# Schematic_2023-04-14.net
KiCad netlist of a schematic drawn in Altium Designer
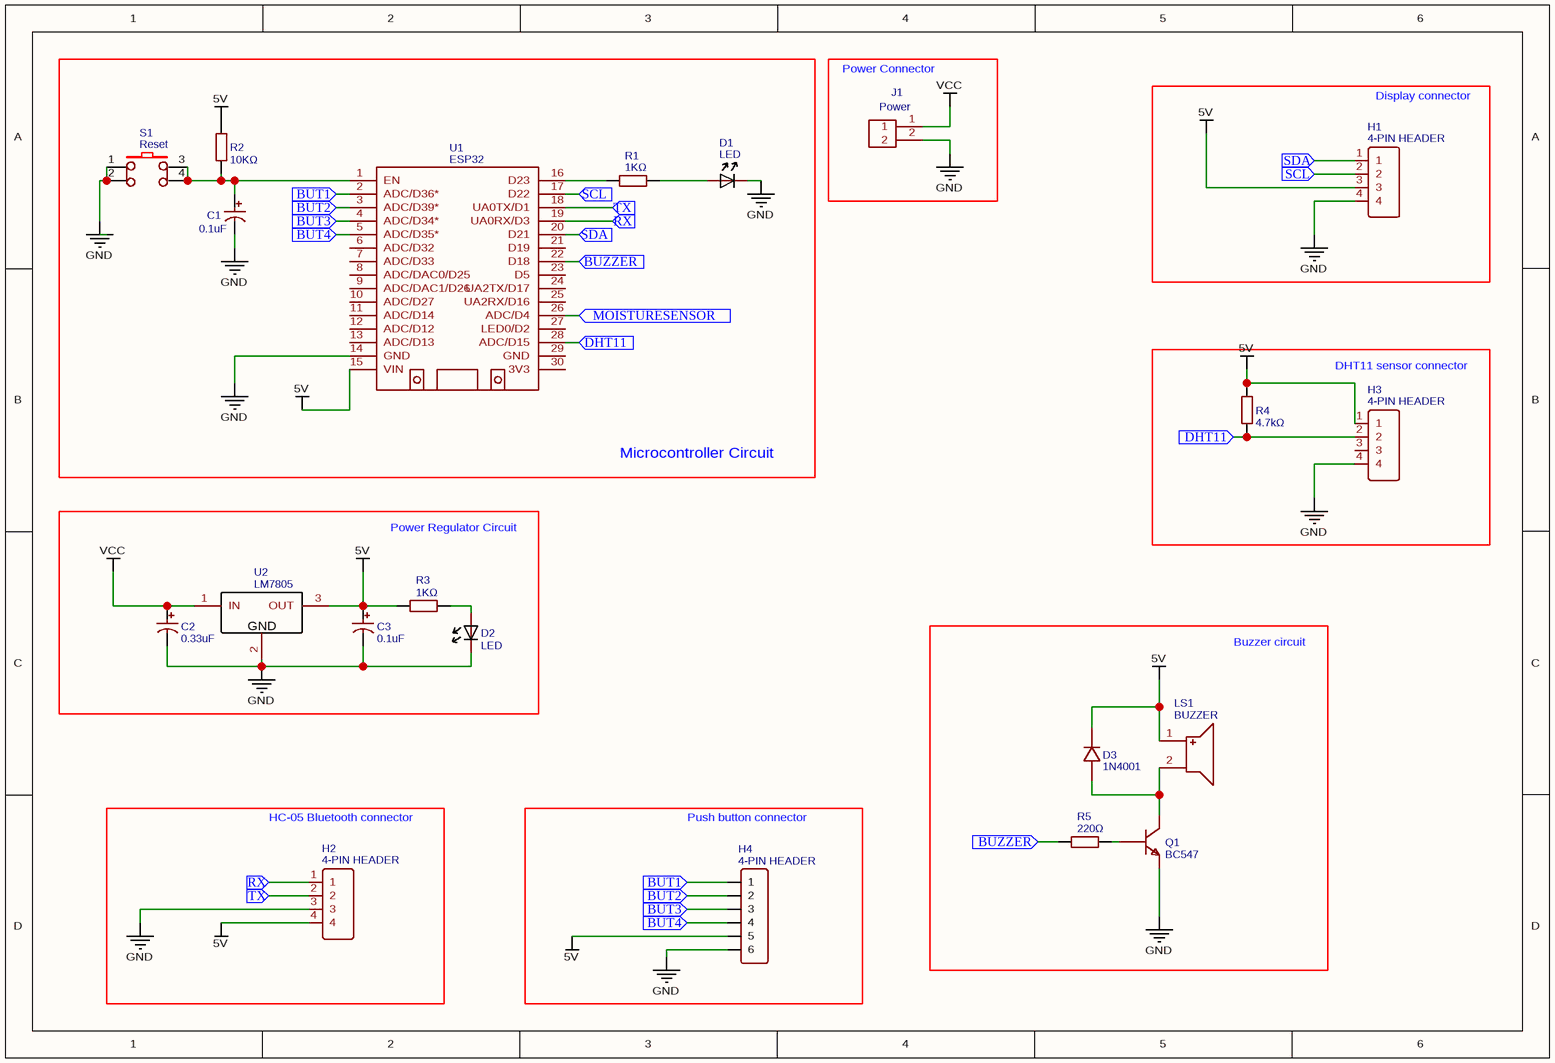
[diagram p0: Schematic_2023-04-14.schdoc]

(export (version "E")
  (design (tool "Eeschema 10.0.6"))
  (components
    (comp (ref "C1")
      (value "0.1uF")
      (fields (field (name "BOM_MANUFACTURER PART") "0.1UF 50V") (field (name "BOM_SUPPLIER PART") "C28061"))
      (libsource (lib "altium-import") (part "root_0_0.1uF_"))
    )
    (comp (ref "C2")
      (value "0.33uF")
      (fields
        (field (name "BOM_MANUFACTURER PART") "0.33uF 50V 5*11")
        (field (name "BOM_SUPPLIER PART") "C45097")
      )
      (libsource (lib "altium-import") (part "root_0_0.33uF_"))
    )
    (comp (ref "C3")
      (value "0.1uF")
      (fields (field (name "BOM_MANUFACTURER PART") "0.1UF 50V") (field (name "BOM_SUPPLIER PART") "C28061"))
      (libsource (lib "altium-import") (part "root_0_0.1uF_"))
    )
    (comp (ref "D1")
      (value "LED")
      (fields (field (name "BOM_MANUFACTURER PART") "5mm LED") (field (name "CONTRIBUTOR") "Axbri"))
      (libsource (lib "altium-import") (part "root_0_LED_"))
    )
    (comp (ref "D2")
      (value "LED")
      (fields (field (name "BOM_MANUFACTURER PART") "5mm LED") (field (name "CONTRIBUTOR") "Axbri"))
      (libsource (lib "altium-import") (part "root_3_LED_"))
    )
    (comp (ref "D3")
      (value "1N4001")
      (fields (field (name "BOM_SUPPLIER PART") "C99656") (field (name "CONTRIBUTOR") "LCSC"))
      (libsource (lib "altium-import") (part "root_3_1N4001_"))
    )
    (comp (ref "H1")
      (value "4-PIN HEADER")
      (fields (field (name "CONTRIBUTOR") "Kang Yi Te"))
      (libsource (lib "altium-import") (part "root_0_4-PIN HEADER_"))
    )
    (comp (ref "H2")
      (value "4-PIN HEADER")
      (fields (field (name "CONTRIBUTOR") "Kang Yi Te"))
      (libsource (lib "altium-import") (part "root_0_4-PIN HEADER_"))
    )
    (comp (ref "H3")
      (value "4-PIN HEADER")
      (fields (field (name "CONTRIBUTOR") "Kang Yi Te"))
      (libsource (lib "altium-import") (part "root_0_4-PIN HEADER_"))
    )
    (comp (ref "H4")
      (value "4-PIN HEADER")
      (fields (field (name "BOM_SUPPLIER PART") "C40877") (field (name "CONTRIBUTOR") "LCEDA_Lib"))
      (libsource (lib "") (part "root_0_4-PIN HEADER__1"))
    )
    (comp (ref "J1")
      (value "Power")
      (fields
        (field (name "BOM_MANUFACTURER PART") "XHB-2A Connector")
        (field (name "BOM_SUPPLIER PART") "C57981")
      )
      (libsource (lib "altium-import") (part "root_0_Power_"))
    )
    (comp (ref "LS1")
      (value "BUZZER")
      (fields
        (field (name "BOM_MANUFACTURER PART") "BUZZERHMB1206-03")
        (field (name "BOM_SUPPLIER PART") "C96101")
        (field (name "CONTRIBUTOR") "วริศรา เกรียงไกรวัฒน์ /ทิพพะ")
      )
      (libsource (lib "altium-import") (part "root_0_BUZZER_"))
    )
    (comp (ref "Q1")
      (value "BC547")
      (fields
        (field (name "BOM_SUPPLIER PART") "C900798")
        (field (name "BOM_MANUFACTURER PART") "BC547BTF")
        (field (name "CONTRIBUTOR") "LCSC")
      )
      (libsource (lib "altium-import") (part "root_0_BC547_"))
    )
    (comp (ref "R1")
      (value "1KΩ")
      (fields
        (field (name "POWER") "1/4W")
        (field (name "TOLERANCE") "±1%")
        (field (name "BOM_SUPPLIER PART") "E57439")
      )
      (libsource (lib "altium-import") (part "root_0_1KΩ_"))
    )
    (comp (ref "R2")
      (value "10KΩ")
      (fields
        (field (name "POWER") "1/4W")
        (field (name "TOLERANCE") "±1%")
        (field (name "BOM_SUPPLIER PART") "E57439")
      )
      (libsource (lib "altium-import") (part "root_3_10KΩ_"))
    )
    (comp (ref "R3")
      (value "1KΩ")
      (fields
        (field (name "POWER") "1/4W")
        (field (name "TOLERANCE") "±1%")
        (field (name "BOM_SUPPLIER PART") "E57439")
      )
      (libsource (lib "altium-import") (part "root_0_1KΩ_"))
    )
    (comp (ref "R4")
      (value "4.7kΩ")
      (fields
        (field (name "POWER") "1/4W")
        (field (name "TOLERANCE") "±1%")
        (field (name "BOM_SUPPLIER PART") "E57439")
      )
      (libsource (lib "altium-import") (part "root_3_4.7kΩ_"))
    )
    (comp (ref "R5")
      (value "220Ω")
      (fields
        (field (name "POWER") "1/4W")
        (field (name "TOLERANCE") "±1%")
        (field (name "BOM_SUPPLIER PART") "E57439")
      )
      (libsource (lib "altium-import") (part "root_0_220Ω_"))
    )
    (comp (ref "S1")
      (value "Reset")
      (fields
        (field (name "BOM_SUPPLIER PART") "C59980")
        (field (name "BOM_MANUFACTURER PART") "button6*6*8.5")
      )
      (libsource (lib "altium-import") (part "root_0_Reset_"))
    )
    (comp (ref "U1")
      (value "ESP32")
      (fields (field (name "CONTRIBUTOR") "ConceitoTeam"))
      (libsource (lib "altium-import") (part "root_0_ESP32_"))
    )
    (comp (ref "U2")
      (value "LM7805")
      (fields
        (field (name "BOM_MANUFACTURER PART") "L7805CV-DG")
        (field (name "BOM_SUPPLIER PART") "C3795")
        (field (name "CONTRIBUTOR") "LCEDA_Lib")
      )
      (libsource (lib "altium-import") (part "root_0_LM7805_"))
    )
  )
  (nets
    (net (code "1") (name "/BUT1") (class "Default")
      (node (ref "H4") (pin "1") (pinfunction "1_1") (pintype "passive"))
      (node (ref "U1") (pin "2") (pinfunction "ADC/D36*_2") (pintype "passive"))
    )
    (net (code "2") (name "/BUT2") (class "Default")
      (node (ref "H4") (pin "2") (pinfunction "2_2") (pintype "passive"))
      (node (ref "U1") (pin "3") (pinfunction "ADC/D39*_3") (pintype "passive"))
    )
    (net (code "3") (name "/BUT3") (class "Default")
      (node (ref "H4") (pin "3") (pinfunction "3_3") (pintype "passive"))
      (node (ref "U1") (pin "4") (pinfunction "ADC/D34*_4") (pintype "passive"))
    )
    (net (code "4") (name "/BUT4") (class "Default")
      (node (ref "H4") (pin "4") (pinfunction "4_4") (pintype "passive"))
      (node (ref "U1") (pin "5") (pinfunction "ADC/D35*_5") (pintype "passive"))
    )
    (net (code "5") (name "/BUZZER") (class "Default")
      (node (ref "R5") (pin "1") (pinfunction "1_1") (pintype "passive"))
      (node (ref "U1") (pin "22") (pinfunction "D18_22") (pintype "passive"))
    )
    (net (code "6") (name "/DHT11") (class "Default")
      (node (ref "H3") (pin "2") (pinfunction "2_2") (pintype "passive"))
      (node (ref "R4") (pin "2") (pinfunction "2_2") (pintype "passive"))
      (node (ref "U1") (pin "28") (pinfunction "ADC/D15_28") (pintype "passive"))
    )
    (net (code "7") (name "/MOISTURESENSOR") (class "Default")
      (node (ref "U1") (pin "26") (pinfunction "ADC/D4_26") (pintype "passive"))
    )
    (net (code "8") (name "/RX") (class "Default")
      (node (ref "H2") (pin "1") (pinfunction "1_1") (pintype "passive"))
      (node (ref "U1") (pin "19") (pinfunction "UA0RX/D3_19") (pintype "passive"))
    )
    (net (code "9") (name "/SCL") (class "Default")
      (node (ref "H1") (pin "2") (pinfunction "2_2") (pintype "passive"))
      (node (ref "U1") (pin "17") (pinfunction "D22_17") (pintype "passive"))
    )
    (net (code "10") (name "/SDA") (class "Default")
      (node (ref "H1") (pin "1") (pinfunction "1_1") (pintype "passive"))
      (node (ref "U1") (pin "20") (pinfunction "D21_20") (pintype "passive"))
    )
    (net (code "11") (name "/TX") (class "Default")
      (node (ref "H2") (pin "2") (pinfunction "2_2") (pintype "passive"))
      (node (ref "U1") (pin "18") (pinfunction "UA0TX/D1_18") (pintype "passive"))
    )
    (net (code "12") (name "5V") (class "Default")
      (node (ref "C3") (pin "1") (pinfunction "1_1") (pintype "passive"))
      (node (ref "D3") (pin "1") (pinfunction "C_1") (pintype "passive"))
      (node (ref "H1") (pin "3") (pinfunction "3_3") (pintype "passive"))
      (node (ref "H2") (pin "4") (pinfunction "4_4") (pintype "passive"))
      (node (ref "H3") (pin "1") (pinfunction "1_1") (pintype "passive"))
      (node (ref "H4") (pin "5") (pinfunction "5_5") (pintype "passive"))
      (node (ref "LS1") (pin "1") (pinfunction "1_1") (pintype "passive"))
      (node (ref "R2") (pin "1") (pinfunction "1_1") (pintype "passive"))
      (node (ref "R3") (pin "1") (pinfunction "1_1") (pintype "passive"))
      (node (ref "R4") (pin "1") (pinfunction "1_1") (pintype "passive"))
      (node (ref "U1") (pin "15") (pinfunction "VIN_15") (pintype "passive"))
      (node (ref "U2") (pin "3") (pinfunction "OUT_3") (pintype "passive"))
    )
    (net (code "13") (name "GND") (class "Default")
      (node (ref "C1") (pin "2") (pinfunction "2_2") (pintype "passive"))
      (node (ref "C2") (pin "2") (pinfunction "2_2") (pintype "passive"))
      (node (ref "C3") (pin "2") (pinfunction "2_2") (pintype "passive"))
      (node (ref "D1") (pin "2") (pinfunction "2_2") (pintype "passive"))
      (node (ref "D2") (pin "2") (pinfunction "2_2") (pintype "passive"))
      (node (ref "H1") (pin "4") (pinfunction "4_4") (pintype "passive"))
      (node (ref "H2") (pin "3") (pinfunction "3_3") (pintype "passive"))
      (node (ref "H3") (pin "4") (pinfunction "4_4") (pintype "passive"))
      (node (ref "H4") (pin "6") (pinfunction "6_6") (pintype "passive"))
      (node (ref "J1") (pin "2") (pinfunction "2_2") (pintype "passive"))
      (node (ref "Q1") (pin "3") (pinfunction "E_3") (pintype "passive"))
      (node (ref "S1") (pin "1") (pinfunction "1_1") (pintype "passive"))
      (node (ref "S1") (pin "2") (pinfunction "2_2") (pintype "passive"))
      (node (ref "U1") (pin "14") (pinfunction "GND_14") (pintype "passive"))
      (node (ref "U2") (pin "2") (pinfunction "GND_2") (pintype "passive"))
    )
    (net (code "14") (name "Net-(D1-Pad1)") (class "Default")
      (node (ref "D1") (pin "1") (pinfunction "1_1") (pintype "passive"))
      (node (ref "R1") (pin "2") (pinfunction "2_2") (pintype "passive"))
    )
    (net (code "15") (name "Net-(D2-Pad1)") (class "Default")
      (node (ref "D2") (pin "1") (pinfunction "1_1") (pintype "passive"))
      (node (ref "R3") (pin "2") (pinfunction "2_2") (pintype "passive"))
    )
    (net (code "16") (name "Net-(D3-A)") (class "Default")
      (node (ref "D3") (pin "2") (pinfunction "A_2") (pintype "passive"))
      (node (ref "LS1") (pin "2") (pinfunction "2_2") (pintype "passive"))
      (node (ref "Q1") (pin "1") (pinfunction "C_1") (pintype "passive"))
    )
    (net (code "17") (name "Net-(Q1-B)") (class "Default")
      (node (ref "Q1") (pin "2") (pinfunction "B_2") (pintype "passive"))
      (node (ref "R5") (pin "2") (pinfunction "2_2") (pintype "passive"))
    )
    (net (code "18") (name "Net-(U1-D23)") (class "Default")
      (node (ref "R1") (pin "1") (pinfunction "1_1") (pintype "passive"))
      (node (ref "U1") (pin "16") (pinfunction "D23_16") (pintype "passive"))
    )
    (net (code "19") (name "Net-(U1-EN)") (class "Default")
      (node (ref "C1") (pin "1") (pinfunction "1_1") (pintype "passive"))
      (node (ref "R2") (pin "2") (pinfunction "2_2") (pintype "passive"))
      (node (ref "S1") (pin "3") (pinfunction "3_3") (pintype "passive"))
      (node (ref "S1") (pin "4") (pinfunction "4_4") (pintype "passive"))
      (node (ref "U1") (pin "1") (pinfunction "EN_1") (pintype "passive"))
    )
    (net (code "20") (name "VCC") (class "Default")
      (node (ref "C2") (pin "1") (pinfunction "1_1") (pintype "passive"))
      (node (ref "J1") (pin "1") (pinfunction "1_1") (pintype "passive"))
      (node (ref "U2") (pin "1") (pinfunction "IN_1") (pintype "passive"))
    )
    (net (code "21") (name "unconnected-(H3-Pad3)") (class "Default")
      (node (ref "H3") (pin "3") (pinfunction "3_3") (pintype "passive"))
    )
    (net (code "22") (name "unconnected-(U1-3V3-Pad30)") (class "Default")
      (node (ref "U1") (pin "30") (pinfunction "3V3_30") (pintype "passive"))
    )
    (net (code "23") (name "unconnected-(U1-ADC{slash}D12-Pad12)") (class "Default")
      (node (ref "U1") (pin "12") (pinfunction "ADC/D12_12") (pintype "passive"))
    )
    (net (code "24") (name "unconnected-(U1-ADC{slash}D13-Pad13)") (class "Default")
      (node (ref "U1") (pin "13") (pinfunction "ADC/D13_13") (pintype "passive"))
    )
    (net (code "25") (name "unconnected-(U1-ADC{slash}D14-Pad11)") (class "Default")
      (node (ref "U1") (pin "11") (pinfunction "ADC/D14_11") (pintype "passive"))
    )
    (net (code "26") (name "unconnected-(U1-ADC{slash}D27-Pad10)") (class "Default")
      (node (ref "U1") (pin "10") (pinfunction "ADC/D27_10") (pintype "passive"))
    )
    (net (code "27") (name "unconnected-(U1-ADC{slash}D32-Pad6)") (class "Default")
      (node (ref "U1") (pin "6") (pinfunction "ADC/D32_6") (pintype "passive"))
    )
    (net (code "28") (name "unconnected-(U1-ADC{slash}D33-Pad7)") (class "Default")
      (node (ref "U1") (pin "7") (pinfunction "ADC/D33_7") (pintype "passive"))
    )
    (net (code "29") (name "unconnected-(U1-ADC{slash}DAC0{slash}D25-Pad8)") (class "Default")
      (node (ref "U1") (pin "8") (pinfunction "ADC/DAC0/D25_8") (pintype "passive"))
    )
    (net (code "30") (name "unconnected-(U1-ADC{slash}DAC1{slash}D26-Pad9)") (class "Default")
      (node (ref "U1") (pin "9") (pinfunction "ADC/DAC1/D26_9") (pintype "passive"))
    )
    (net (code "31") (name "unconnected-(U1-D5-Pad23)") (class "Default")
      (node (ref "U1") (pin "23") (pinfunction "D5_23") (pintype "passive"))
    )
    (net (code "32") (name "unconnected-(U1-D19-Pad21)") (class "Default")
      (node (ref "U1") (pin "21") (pinfunction "D19_21") (pintype "passive"))
    )
    (net (code "33") (name "unconnected-(U1-GND-Pad29)") (class "Default")
      (node (ref "U1") (pin "29") (pinfunction "GND_29") (pintype "passive"))
    )
    (net (code "34") (name "unconnected-(U1-LED0{slash}D2-Pad27)") (class "Default")
      (node (ref "U1") (pin "27") (pinfunction "LED0/D2_27") (pintype "passive"))
    )
    (net (code "35") (name "unconnected-(U1-UA2RX{slash}D16-Pad25)") (class "Default")
      (node (ref "U1") (pin "25") (pinfunction "UA2RX/D16_25") (pintype "passive"))
    )
    (net (code "36") (name "unconnected-(U1-UA2TX{slash}D17-Pad24)") (class "Default")
      (node (ref "U1") (pin "24") (pinfunction "UA2TX/D17_24") (pintype "passive"))
    )
  )
)
